# power.net
KiCad netlist of a schematic drawn in Altium Designer
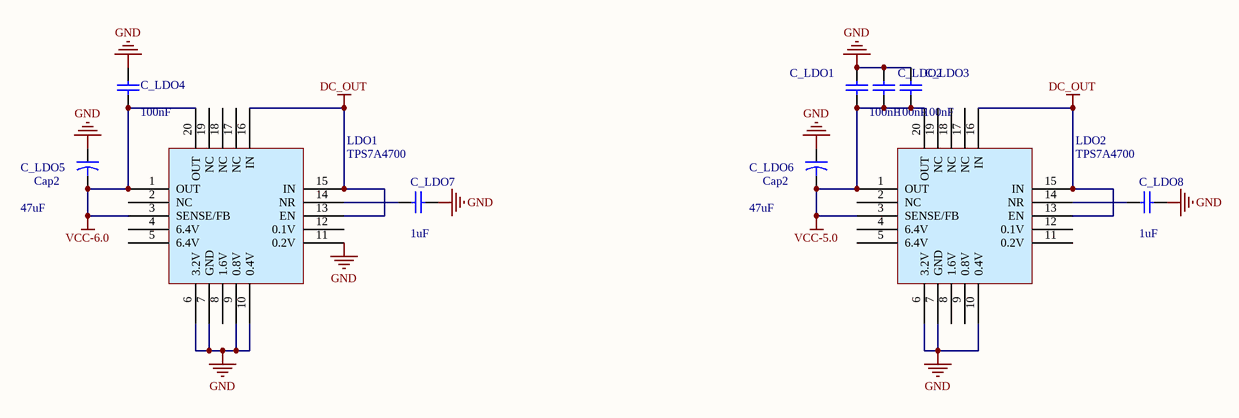
[diagram p0: power.SchDoc]

(export (version "E")
  (design (tool "Eeschema 10.0.6"))
  (components
    (comp (ref "C_LDO1")
      (value "100nF")
      (footprint "0805")
      (description "Capacitor")
      (fields (field (name "PUBLISHER") "Altium Limited"))
      (libsource (lib "Miscellaneous Devices") (part "Cap"))
    )
    (comp (ref "C_LDO2")
      (value "100nF")
      (footprint "0805")
      (description "Capacitor")
      (fields (field (name "PUBLISHER") "Altium Limited"))
      (libsource (lib "Miscellaneous Devices") (part "Cap"))
    )
    (comp (ref "C_LDO3")
      (value "100nF")
      (footprint "0805")
      (description "Capacitor")
      (fields (field (name "PUBLISHER") "Altium Limited"))
      (libsource (lib "Miscellaneous Devices") (part "Cap"))
    )
    (comp (ref "C_LDO4")
      (value "100nF")
      (footprint "0805")
      (description "Capacitor")
      (fields (field (name "PUBLISHER") "Altium Limited"))
      (libsource (lib "Miscellaneous Devices") (part "Cap"))
    )
    (comp (ref "C_LDO5")
      (value "Cap2")
      (footprint "1210")
      (description "Capacitor")
      (fields (field (name "ALTIUM_VALUE") "47uF") (field (name "PUBLISHER") "Altium Limited"))
      (libsource (lib "Miscellaneous Devices") (part "Cap2"))
    )
    (comp (ref "C_LDO6")
      (value "Cap2")
      (footprint "1210")
      (description "Capacitor")
      (fields (field (name "ALTIUM_VALUE") "47uF") (field (name "PUBLISHER") "Altium Limited"))
      (libsource (lib "Miscellaneous Devices") (part "Cap2"))
    )
    (comp (ref "C_LDO7")
      (value "1uF")
      (footprint "0603")
      (description "Capacitor")
      (fields (field (name "PUBLISHER") "Altium Limited"))
      (libsource (lib "Miscellaneous Devices") (part "Cap"))
    )
    (comp (ref "C_LDO8")
      (value "1uF")
      (footprint "0603")
      (description "Capacitor")
      (fields (field (name "PUBLISHER") "Altium Limited"))
      (libsource (lib "Miscellaneous Devices") (part "Cap"))
    )
    (comp (ref "LDO1")
      (value "TPS7A4700")
      (footprint "TPS7A4700 - b")
      (libsource (lib "complements") (part "TPS7A4700"))
    )
    (comp (ref "LDO2")
      (value "TPS7A4700")
      (footprint "TPS7A4700 - b")
      (libsource (lib "complements") (part "TPS7A4700"))
    )
  )
  (nets
    (net (code "1") (name "DC_OUT") (class "Default")
      (node (ref "LDO1") (pin "13") (pinfunction "EN_13") (pintype "passive"))
      (node (ref "LDO1") (pin "15") (pinfunction "IN_15") (pintype "passive"))
      (node (ref "LDO1") (pin "16") (pinfunction "IN_16") (pintype "passive"))
      (node (ref "LDO2") (pin "13") (pinfunction "EN_13") (pintype "passive"))
      (node (ref "LDO2") (pin "15") (pinfunction "IN_15") (pintype "passive"))
      (node (ref "LDO2") (pin "16") (pinfunction "IN_16") (pintype "passive"))
    )
    (net (code "2") (name "GND") (class "Default")
      (node (ref "C_LDO1") (pin "1") (pinfunction "1_1") (pintype "passive"))
      (node (ref "C_LDO2") (pin "1") (pinfunction "1_1") (pintype "passive"))
      (node (ref "C_LDO3") (pin "1") (pinfunction "1_1") (pintype "passive"))
      (node (ref "C_LDO4") (pin "1") (pinfunction "1_1") (pintype "passive"))
      (node (ref "C_LDO5") (pin "1") (pinfunction "1_1") (pintype "passive"))
      (node (ref "C_LDO6") (pin "1") (pinfunction "1_1") (pintype "passive"))
      (node (ref "C_LDO7") (pin "1") (pinfunction "1_1") (pintype "passive"))
      (node (ref "C_LDO8") (pin "1") (pinfunction "1_1") (pintype "passive"))
      (node (ref "LDO1") (pin "10") (pinfunction "0.4V_10") (pintype "passive"))
      (node (ref "LDO1") (pin "11") (pinfunction "0.2V_11") (pintype "passive"))
      (node (ref "LDO1") (pin "6") (pinfunction "3.2V_6") (pintype "passive"))
      (node (ref "LDO1") (pin "7") (pinfunction "GND_7") (pintype "passive"))
      (node (ref "LDO1") (pin "9") (pinfunction "0.8V_9") (pintype "passive"))
      (node (ref "LDO2") (pin "10") (pinfunction "0.4V_10") (pintype "passive"))
      (node (ref "LDO2") (pin "6") (pinfunction "3.2V_6") (pintype "passive"))
      (node (ref "LDO2") (pin "7") (pinfunction "GND_7") (pintype "passive"))
    )
    (net (code "3") (name "Net-(LDO1-NR)") (class "Default")
      (node (ref "C_LDO7") (pin "2") (pinfunction "2_2") (pintype "passive"))
      (node (ref "LDO1") (pin "14") (pinfunction "NR_14") (pintype "passive"))
    )
    (net (code "4") (name "Net-(LDO2-NR)") (class "Default")
      (node (ref "C_LDO8") (pin "2") (pinfunction "2_2") (pintype "passive"))
      (node (ref "LDO2") (pin "14") (pinfunction "NR_14") (pintype "passive"))
    )
    (net (code "5") (name "VCC-5.0") (class "Default")
      (node (ref "C_LDO1") (pin "2") (pinfunction "2_2") (pintype "passive"))
      (node (ref "C_LDO2") (pin "2") (pinfunction "2_2") (pintype "passive"))
      (node (ref "C_LDO3") (pin "2") (pinfunction "2_2") (pintype "passive"))
      (node (ref "C_LDO6") (pin "2") (pinfunction "2_2") (pintype "passive"))
      (node (ref "LDO2") (pin "1") (pinfunction "OUT_1") (pintype "passive"))
      (node (ref "LDO2") (pin "20") (pinfunction "OUT_20") (pintype "passive"))
      (node (ref "LDO2") (pin "3") (pinfunction "SENSE/FB_3") (pintype "passive"))
    )
    (net (code "6") (name "VCC-6.0") (class "Default")
      (node (ref "C_LDO4") (pin "2") (pinfunction "2_2") (pintype "passive"))
      (node (ref "C_LDO5") (pin "2") (pinfunction "2_2") (pintype "passive"))
      (node (ref "LDO1") (pin "1") (pinfunction "OUT_1") (pintype "passive"))
      (node (ref "LDO1") (pin "20") (pinfunction "OUT_20") (pintype "passive"))
      (node (ref "LDO1") (pin "3") (pinfunction "SENSE/FB_3") (pintype "passive"))
    )
    (net (code "7") (name "unconnected-(LDO1-0.1V-Pad12)") (class "Default")
      (node (ref "LDO1") (pin "12") (pinfunction "0.1V_12") (pintype "passive"))
    )
    (net (code "8") (name "unconnected-(LDO1-1.6V-Pad8)") (class "Default")
      (node (ref "LDO1") (pin "8") (pinfunction "1.6V_8") (pintype "passive"))
    )
    (net (code "9") (name "unconnected-(LDO1-6.4V-Pad4)") (class "Default")
      (node (ref "LDO1") (pin "4") (pinfunction "6.4V_4") (pintype "passive"))
    )
    (net (code "10") (name "unconnected-(LDO1-6.4V-Pad5)") (class "Default")
      (node (ref "LDO1") (pin "5") (pinfunction "6.4V_5") (pintype "passive"))
    )
    (net (code "11") (name "unconnected-(LDO1-NC-Pad2)") (class "Default")
      (node (ref "LDO1") (pin "2") (pinfunction "NC_2") (pintype "passive"))
    )
    (net (code "12") (name "unconnected-(LDO1-NC-Pad17)") (class "Default")
      (node (ref "LDO1") (pin "17") (pinfunction "NC_17") (pintype "passive"))
    )
    (net (code "13") (name "unconnected-(LDO1-NC-Pad18)") (class "Default")
      (node (ref "LDO1") (pin "18") (pinfunction "NC_18") (pintype "passive"))
    )
    (net (code "14") (name "unconnected-(LDO1-NC-Pad19)") (class "Default")
      (node (ref "LDO1") (pin "19") (pinfunction "NC_19") (pintype "passive"))
    )
    (net (code "15") (name "unconnected-(LDO2-0.1V-Pad12)") (class "Default")
      (node (ref "LDO2") (pin "12") (pinfunction "0.1V_12") (pintype "passive"))
    )
    (net (code "16") (name "unconnected-(LDO2-0.2V-Pad11)") (class "Default")
      (node (ref "LDO2") (pin "11") (pinfunction "0.2V_11") (pintype "passive"))
    )
    (net (code "17") (name "unconnected-(LDO2-0.8V-Pad9)") (class "Default")
      (node (ref "LDO2") (pin "9") (pinfunction "0.8V_9") (pintype "passive"))
    )
    (net (code "18") (name "unconnected-(LDO2-1.6V-Pad8)") (class "Default")
      (node (ref "LDO2") (pin "8") (pinfunction "1.6V_8") (pintype "passive"))
    )
    (net (code "19") (name "unconnected-(LDO2-6.4V-Pad4)") (class "Default")
      (node (ref "LDO2") (pin "4") (pinfunction "6.4V_4") (pintype "passive"))
    )
    (net (code "20") (name "unconnected-(LDO2-6.4V-Pad5)") (class "Default")
      (node (ref "LDO2") (pin "5") (pinfunction "6.4V_5") (pintype "passive"))
    )
    (net (code "21") (name "unconnected-(LDO2-NC-Pad2)") (class "Default")
      (node (ref "LDO2") (pin "2") (pinfunction "NC_2") (pintype "passive"))
    )
    (net (code "22") (name "unconnected-(LDO2-NC-Pad17)") (class "Default")
      (node (ref "LDO2") (pin "17") (pinfunction "NC_17") (pintype "passive"))
    )
    (net (code "23") (name "unconnected-(LDO2-NC-Pad18)") (class "Default")
      (node (ref "LDO2") (pin "18") (pinfunction "NC_18") (pintype "passive"))
    )
    (net (code "24") (name "unconnected-(LDO2-NC-Pad19)") (class "Default")
      (node (ref "LDO2") (pin "19") (pinfunction "NC_19") (pintype "passive"))
    )
  )
)
